# poiduino7.net
KiCad netlist of a schematic drawn in EAGLE
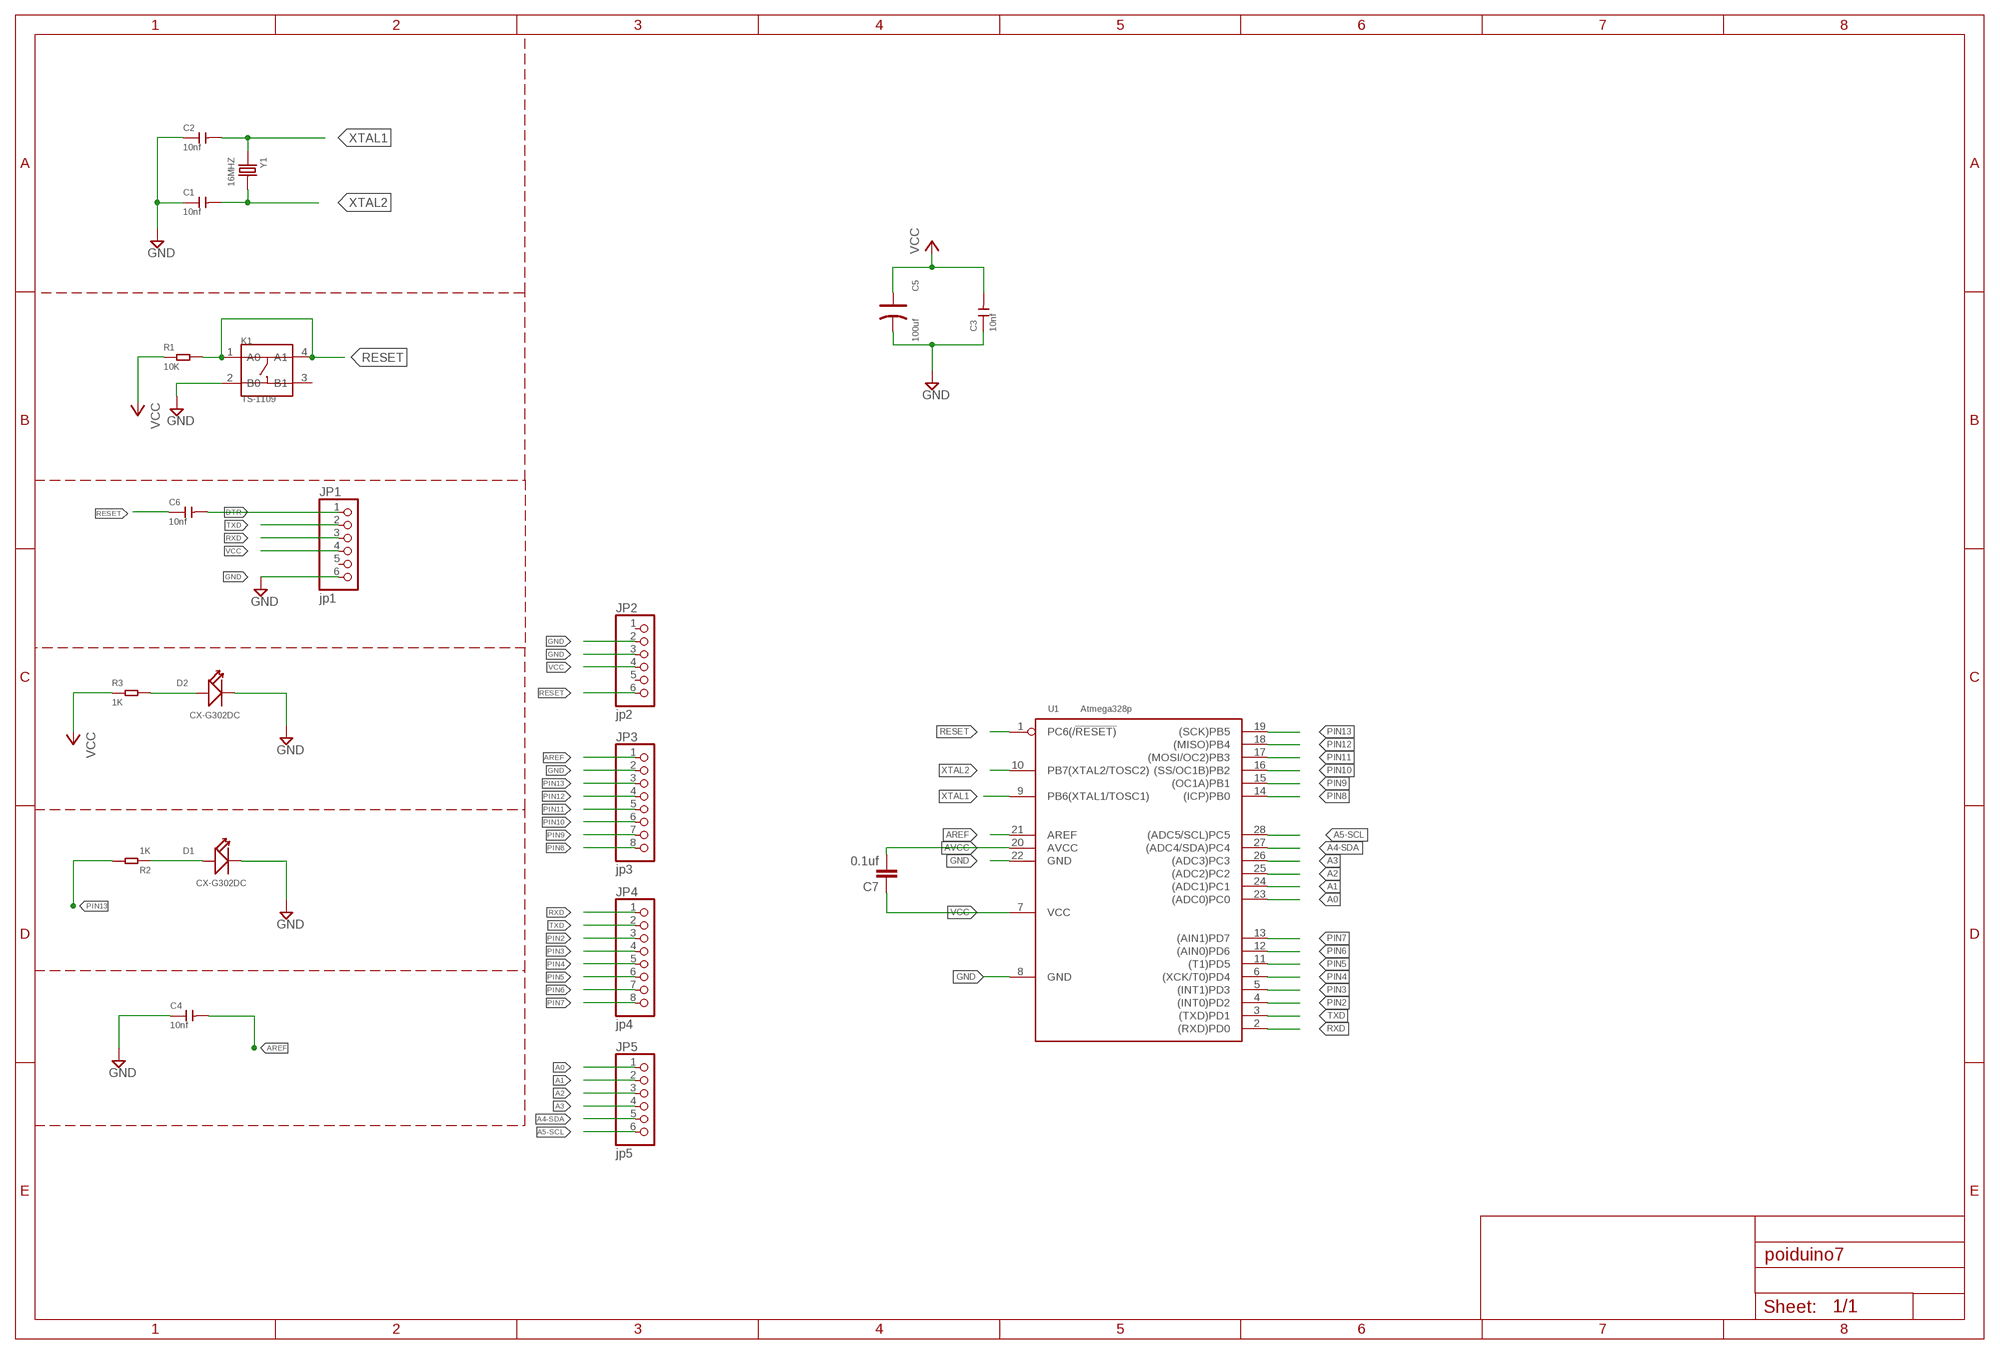
[diagram p0: schematic, sheet 1]

(export (version "E")
  (design (tool "Eeschema 10.0.6"))
  (components
    (comp (ref "C1")
      (value "10nf")
      (footprint "eagle-import:CERAMIC-2.54")
      (libsource (lib "eagle-import") (part "DIP-CERAMIC-DISC-10NF-50V-Y5V(D4.0MM)"))
    )
    (comp (ref "C2")
      (value "10nf")
      (footprint "eagle-import:CERAMIC-2.54")
      (libsource (lib "eagle-import") (part "DIP-CERAMIC-DISC-10NF-50V-Y5V(D4.0MM)"))
    )
    (comp (ref "C3")
      (value "10nf")
      (footprint "eagle-import:CERAMIC-2.54")
      (libsource (lib "eagle-import") (part "DIP-CERAMIC-DISC-10NF-50V-Y5V(D4.0MM)"))
    )
    (comp (ref "C4")
      (value "10nf")
      (footprint "eagle-import:CERAMIC-2.54")
      (libsource (lib "eagle-import") (part "DIP-CERAMIC-DISC-10NF-50V-Y5V(D4.0MM)"))
    )
    (comp (ref "C5")
      (value "100uf")
      (footprint "eagle-import:PC-D5.3MM")
      (fields (field (name "MPN") "KS 100uF/16V"))
      (libsource (lib "eagle-import") (part "DIP-ALUMINUM-47UF-16V(D5-H7MM)"))
    )
    (comp (ref "C6")
      (value "10nf")
      (footprint "eagle-import:CERAMIC-2.54")
      (libsource (lib "eagle-import") (part "DIP-CERAMIC-DISC-10NF-50V-Y5V(D4.0MM)"))
    )
    (comp (ref "C7")
      (value "0.1uf")
      (footprint "eagle-import:C5B2.5")
      (libsource (lib "eagle-import") (part "C5/2.5"))
    )
    (comp (ref "D1")
      (value "CX-G302DC")
      (footprint "eagle-import:LED2-2.54-D3.0MM")
      (libsource (lib "eagle-import") (part "DIP-LED-GREEN-GREEN(2P-D3MM)"))
    )
    (comp (ref "D2")
      (value "CX-G302DC")
      (footprint "eagle-import:LED2-2.54-D3.0MM")
      (libsource (lib "eagle-import") (part "DIP-LED-GREEN-GREEN(2P-D3MM)"))
    )
    (comp (ref "JP1")
      (value "jp1")
      (footprint "eagle-import:1X06")
      (libsource (lib "eagle-import") (part "PINHD-1X6"))
    )
    (comp (ref "JP2")
      (value "jp2")
      (footprint "eagle-import:1X06")
      (libsource (lib "eagle-import") (part "PINHD-1X6"))
    )
    (comp (ref "JP3")
      (value "jp3")
      (footprint "eagle-import:1X08")
      (libsource (lib "eagle-import") (part "PINHD-1X8"))
    )
    (comp (ref "JP4")
      (value "jp4")
      (footprint "eagle-import:1X08")
      (libsource (lib "eagle-import") (part "PINHD-1X8"))
    )
    (comp (ref "JP5")
      (value "jp5")
      (footprint "eagle-import:1X06")
      (libsource (lib "eagle-import") (part "PINHD-1X6"))
    )
    (comp (ref "K1")
      (value "TS-1109")
      (footprint "eagle-import:SW4-6.0X6.0X5.0MM")
      (libsource (lib "eagle-import") (part "DIP-BUTTON-4P"))
    )
    (comp (ref "R1")
      (value "10K")
      (footprint "eagle-import:PR-D2.3XL6.5MM")
      (fields (field (name "MPN") "FHCFR-1/4W-103J"))
      (libsource (lib "eagle-import") (part "DIP-RES-10K-5%-1/4W(PR-D2.3XL6.5MM)"))
    )
    (comp (ref "R2")
      (value "1K")
      (footprint "eagle-import:PR-D2.3XL6.5MM")
      (fields (field (name "MPN") "FHCFR-1/4W-102J"))
      (libsource (lib "eagle-import") (part "DIP-RES-1K-5%-1/4W(PR-D2.3XL6.5MM)"))
    )
    (comp (ref "R3")
      (value "1K")
      (footprint "eagle-import:PR-D2.3XL6.5MM")
      (fields (field (name "MPN") "FHCFR-1/4W-102J"))
      (libsource (lib "eagle-import") (part "DIP-RES-1K-5%-1/4W(PR-D2.3XL6.5MM)"))
    )
    (comp (ref "U1")
      (value "Atmega328p")
      (footprint "eagle-import:DIP28-2.54-34.7X7.62MM")
      (fields (field (name "MPN") "ATMEGA328P-PU"))
      (libsource (lib "eagle-import") (part "MCU-ATMEGA328P-PU(DIP28)"))
    )
    (comp (ref "Y1")
      (value "16MHZ")
      (footprint "eagle-import:HC49US")
      (fields (field (name "MPN") "HC-49US    16.000MHz"))
      (libsource (lib "eagle-import") (part "DIP-CRYSTAL-16MHZ-18PF-30PPM-40R(HC49US)"))
    )
  )
  (nets
    (net (code "1") (name "A0") (class "Default")
      (node (ref "JP5") (pin "1") (pinfunction "1_1") (pintype "passive"))
      (node (ref "U1") (pin "23") (pinfunction "(ADC0)PC0_23") (pintype "bidirectional"))
    )
    (net (code "2") (name "A1") (class "Default")
      (node (ref "JP5") (pin "2") (pinfunction "2_2") (pintype "passive"))
      (node (ref "U1") (pin "24") (pinfunction "(ADC1)PC1_24") (pintype "bidirectional"))
    )
    (net (code "3") (name "A2") (class "Default")
      (node (ref "JP5") (pin "3") (pinfunction "3_3") (pintype "passive"))
      (node (ref "U1") (pin "25") (pinfunction "(ADC2)PC2_25") (pintype "bidirectional"))
    )
    (net (code "4") (name "A3") (class "Default")
      (node (ref "JP5") (pin "4") (pinfunction "4_4") (pintype "passive"))
      (node (ref "U1") (pin "26") (pinfunction "(ADC3)PC3_26") (pintype "bidirectional"))
    )
    (net (code "5") (name "A4-SDA") (class "Default")
      (node (ref "JP5") (pin "5") (pinfunction "5_5") (pintype "passive"))
      (node (ref "U1") (pin "27") (pinfunction "(ADC4/SDA)PC4_27") (pintype "bidirectional"))
    )
    (net (code "6") (name "A5-SCL") (class "Default")
      (node (ref "JP5") (pin "6") (pinfunction "6_6") (pintype "passive"))
      (node (ref "U1") (pin "28") (pinfunction "(ADC5/SCL)PC5_28") (pintype "bidirectional"))
    )
    (net (code "7") (name "AREF") (class "Default")
      (node (ref "C4") (pin "2") (pinfunction "2_2") (pintype "passive"))
      (node (ref "JP3") (pin "1") (pinfunction "1_1") (pintype "passive"))
      (node (ref "U1") (pin "21") (pinfunction "AREF_21") (pintype "bidirectional"))
    )
    (net (code "8") (name "AVCC") (class "Default")
      (node (ref "C7") (pin "2") (pinfunction "2_2") (pintype "passive"))
      (node (ref "U1") (pin "20") (pinfunction "AVCC_20") (pintype "bidirectional"))
    )
    (net (code "9") (name "DTR") (class "Default")
      (node (ref "C6") (pin "2") (pinfunction "2_2") (pintype "passive"))
      (node (ref "JP1") (pin "1") (pinfunction "1_1") (pintype "passive"))
    )
    (net (code "10") (name "GND") (class "Default")
      (node (ref "C1") (pin "1") (pinfunction "1_1") (pintype "passive"))
      (node (ref "C2") (pin "1") (pinfunction "1_1") (pintype "passive"))
      (node (ref "C3") (pin "1") (pinfunction "1_1") (pintype "passive"))
      (node (ref "C4") (pin "1") (pinfunction "1_1") (pintype "passive"))
      (node (ref "C5") (pin "-") (pinfunction "-_-") (pintype "passive"))
      (node (ref "D1") (pin "K") (pinfunction "-_K") (pintype "passive"))
      (node (ref "D2") (pin "K") (pinfunction "-_K") (pintype "passive"))
      (node (ref "JP1") (pin "6") (pinfunction "6_6") (pintype "passive"))
      (node (ref "JP2") (pin "2") (pinfunction "2_2") (pintype "passive"))
      (node (ref "JP2") (pin "3") (pinfunction "3_3") (pintype "passive"))
      (node (ref "JP3") (pin "2") (pinfunction "2_2") (pintype "passive"))
      (node (ref "K1") (pin "2") (pinfunction "B0_2") (pintype "bidirectional"))
      (node (ref "U1") (pin "22") (pinfunction "GND_22") (pintype "bidirectional"))
      (node (ref "U1") (pin "8") (pinfunction "GND_8") (pintype "bidirectional"))
    )
    (net (code "11") (name "Net-(D1-+)") (class "Default")
      (node (ref "D1") (pin "A") (pinfunction "+_A") (pintype "passive"))
      (node (ref "R2") (pin "1") (pinfunction "1_1") (pintype "passive"))
    )
    (net (code "12") (name "Net-(D2-+)") (class "Default")
      (node (ref "D2") (pin "A") (pinfunction "+_A") (pintype "passive"))
      (node (ref "R3") (pin "2") (pinfunction "2_2") (pintype "passive"))
    )
    (net (code "13") (name "PIN2") (class "Default")
      (node (ref "JP4") (pin "3") (pinfunction "3_3") (pintype "passive"))
      (node (ref "U1") (pin "4") (pinfunction "(INT0)PD2_4") (pintype "bidirectional"))
    )
    (net (code "14") (name "PIN3") (class "Default")
      (node (ref "JP4") (pin "4") (pinfunction "4_4") (pintype "passive"))
      (node (ref "U1") (pin "5") (pinfunction "(INT1)PD3_5") (pintype "bidirectional"))
    )
    (net (code "15") (name "PIN4") (class "Default")
      (node (ref "JP4") (pin "5") (pinfunction "5_5") (pintype "passive"))
      (node (ref "U1") (pin "6") (pinfunction "(XCK/T0)PD4_6") (pintype "bidirectional"))
    )
    (net (code "16") (name "PIN5") (class "Default")
      (node (ref "JP4") (pin "6") (pinfunction "6_6") (pintype "passive"))
      (node (ref "U1") (pin "11") (pinfunction "(T1)PD5_11") (pintype "bidirectional"))
    )
    (net (code "17") (name "PIN6") (class "Default")
      (node (ref "JP4") (pin "7") (pinfunction "7_7") (pintype "passive"))
      (node (ref "U1") (pin "12") (pinfunction "(AIN0)PD6_12") (pintype "bidirectional"))
    )
    (net (code "18") (name "PIN7") (class "Default")
      (node (ref "JP4") (pin "8") (pinfunction "8_8") (pintype "passive"))
      (node (ref "U1") (pin "13") (pinfunction "(AIN1)PD7_13") (pintype "bidirectional"))
    )
    (net (code "19") (name "PIN8") (class "Default")
      (node (ref "JP3") (pin "8") (pinfunction "8_8") (pintype "passive"))
      (node (ref "U1") (pin "14") (pinfunction "(ICP)PB0_14") (pintype "bidirectional"))
    )
    (net (code "20") (name "PIN9") (class "Default")
      (node (ref "JP3") (pin "7") (pinfunction "7_7") (pintype "passive"))
      (node (ref "U1") (pin "15") (pinfunction "(OC1A)PB1_15") (pintype "bidirectional"))
    )
    (net (code "21") (name "PIN10") (class "Default")
      (node (ref "JP3") (pin "6") (pinfunction "6_6") (pintype "passive"))
      (node (ref "U1") (pin "16") (pinfunction "(SS/OC1B)PB2_16") (pintype "bidirectional"))
    )
    (net (code "22") (name "PIN11") (class "Default")
      (node (ref "JP3") (pin "5") (pinfunction "5_5") (pintype "passive"))
      (node (ref "U1") (pin "17") (pinfunction "(MOSI/OC2)PB3_17") (pintype "bidirectional"))
    )
    (net (code "23") (name "PIN12") (class "Default")
      (node (ref "JP3") (pin "4") (pinfunction "4_4") (pintype "passive"))
      (node (ref "U1") (pin "18") (pinfunction "(MISO)PB4_18") (pintype "bidirectional"))
    )
    (net (code "24") (name "PIN13") (class "Default")
      (node (ref "JP3") (pin "3") (pinfunction "3_3") (pintype "passive"))
      (node (ref "R2") (pin "2") (pinfunction "2_2") (pintype "passive"))
      (node (ref "U1") (pin "19") (pinfunction "(SCK)PB5_19") (pintype "bidirectional"))
    )
    (net (code "25") (name "RESET") (class "Default")
      (node (ref "C6") (pin "1") (pinfunction "1_1") (pintype "passive"))
      (node (ref "JP2") (pin "6") (pinfunction "6_6") (pintype "passive"))
      (node (ref "K1") (pin "1") (pinfunction "A0_1") (pintype "bidirectional"))
      (node (ref "K1") (pin "4") (pinfunction "A1_4") (pintype "bidirectional"))
      (node (ref "R1") (pin "2") (pinfunction "2_2") (pintype "passive"))
      (node (ref "U1") (pin "1") (pinfunction "PC6(/~{RESET})_1") (pintype "bidirectional"))
    )
    (net (code "26") (name "RXD") (class "Default")
      (node (ref "JP1") (pin "3") (pinfunction "3_3") (pintype "passive"))
      (node (ref "JP4") (pin "1") (pinfunction "1_1") (pintype "passive"))
      (node (ref "U1") (pin "2") (pinfunction "(RXD)PD0_2") (pintype "bidirectional"))
    )
    (net (code "27") (name "TXD") (class "Default")
      (node (ref "JP1") (pin "2") (pinfunction "2_2") (pintype "passive"))
      (node (ref "JP4") (pin "2") (pinfunction "2_2") (pintype "passive"))
      (node (ref "U1") (pin "3") (pinfunction "(TXD)PD1_3") (pintype "bidirectional"))
    )
    (net (code "28") (name "VCC") (class "Default")
      (node (ref "C3") (pin "2") (pinfunction "2_2") (pintype "passive"))
      (node (ref "C5") (pin "+") (pinfunction "+_+") (pintype "passive"))
      (node (ref "C7") (pin "1") (pinfunction "1_1") (pintype "passive"))
      (node (ref "JP1") (pin "4") (pinfunction "4_4") (pintype "passive"))
      (node (ref "JP2") (pin "4") (pinfunction "4_4") (pintype "passive"))
      (node (ref "R1") (pin "1") (pinfunction "1_1") (pintype "passive"))
      (node (ref "R3") (pin "1") (pinfunction "1_1") (pintype "passive"))
      (node (ref "U1") (pin "7") (pinfunction "VCC_7") (pintype "bidirectional"))
    )
    (net (code "29") (name "XTAL1") (class "Default")
      (node (ref "C2") (pin "2") (pinfunction "2_2") (pintype "passive"))
      (node (ref "U1") (pin "9") (pinfunction "PB6(XTAL1/TOSC1)_9") (pintype "bidirectional"))
      (node (ref "Y1") (pin "1") (pinfunction "1_1") (pintype "passive"))
    )
    (net (code "30") (name "XTAL2") (class "Default")
      (node (ref "C1") (pin "2") (pinfunction "2_2") (pintype "passive"))
      (node (ref "U1") (pin "10") (pinfunction "PB7(XTAL2/TOSC2)_10") (pintype "bidirectional"))
      (node (ref "Y1") (pin "2") (pinfunction "2_2") (pintype "passive"))
    )
    (net (code "31") (name "unconnected-(JP1-Pad5)") (class "Default")
      (node (ref "JP1") (pin "5") (pinfunction "5_5") (pintype "passive"))
    )
    (net (code "32") (name "unconnected-(JP2-Pad1)") (class "Default")
      (node (ref "JP2") (pin "1") (pinfunction "1_1") (pintype "passive"))
    )
    (net (code "33") (name "unconnected-(JP2-Pad5)") (class "Default")
      (node (ref "JP2") (pin "5") (pinfunction "5_5") (pintype "passive"))
    )
    (net (code "34") (name "unconnected-(K1-B1-Pad3)") (class "Default")
      (node (ref "K1") (pin "3") (pinfunction "B1_3") (pintype "bidirectional"))
    )
  )
)
